# GPS-Board.net
KiCad netlist of a schematic drawn in Altium Designer
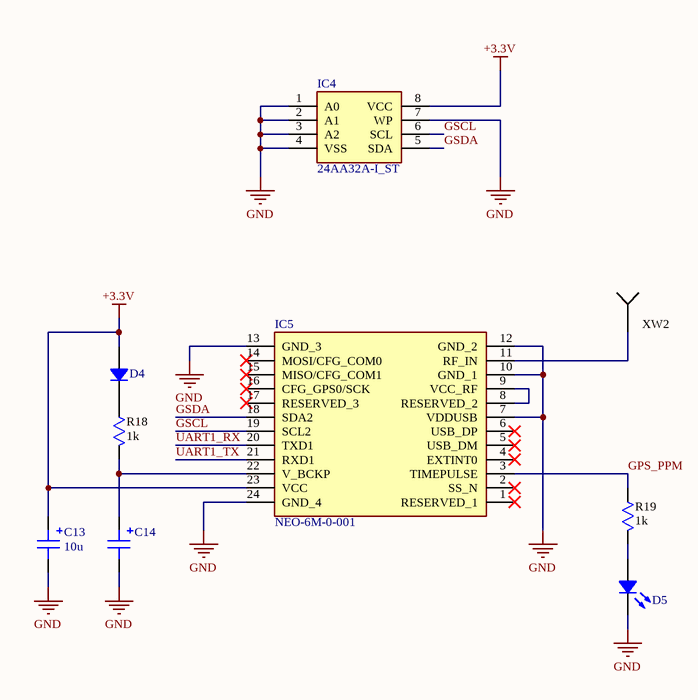
[diagram p0: GPS-Board.SchDoc]

(export (version "E")
  (design (tool "Eeschema 10.0.6"))
  (components
    (comp (ref "C13")
      (value "10u")
      (footprint "PcbLib:CAP: TANTAL-A")
      (description "SMD Capacitor Polar")
      (libsource (lib "Schlib") (part "Capacitor_polar"))
    )
    (comp (ref "C14")
      (value "~")
      (footprint "CAP: IONISTOR")
      (description "SMD Capacitor Polar")
      (libsource (lib "Schlib") (part "Capacitor_polar"))
    )
    (comp (ref "D4")
      (value "~")
      (footprint "PcbLib:DIODE: SOD323")
      (description "Rectifier Diode")
      (libsource (lib "Schlib") (part "Diode"))
    )
    (comp (ref "D5")
      (value "~")
      (footprint "PcbLib:LED 0603_1608")
      (description "Chip LED")
      (libsource (lib "Schlib") (part "LED"))
    )
    (comp (ref "IC4")
      (value "24AA32A-I_ST")
      (footprint "PcbLib:SOP65P640X120-8N")
      (description "Integrated Circuit")
      (fields
        (field (name "MANUFACTURER_PART_NUMBER") "24AA32A-I/ST")
        (field (name "MOUSER PART NUMBER") "579-24AA32A-I/ST")
      )
      (libsource (lib "*") (part "24AA32A-I_ST"))
    )
    (comp (ref "IC5")
      (value "NEO-6M-0-001")
      (footprint "PcbLib:NEO6M0001")
      (description "Integrated Circuit")
      (libsource (lib "*") (part "NEO-6M-0-001"))
    )
    (comp (ref "R18")
      (value "1k")
      (footprint "PcbLib:RES: 0603")
      (fields
        (field (name "MANUFACTURER") "Yageo")
        (field (name "PARTNUMBER") "RC0201JR-07100RL")
        (field (name "VALUEMANUFACTURERPARTNUMBER") "Resistor film, 1k, , 0201, 0.05W, -55...+125°C")
      )
      (libsource (lib "Schlib") (part "Resistor"))
    )
    (comp (ref "R19")
      (value "1k")
      (footprint "PcbLib:RES: 0603")
      (fields
        (field (name "MANUFACTURER") "Yageo")
        (field (name "PARTNUMBER") "RC0201JR-07100RL")
        (field (name "VALUEMANUFACTURERPARTNUMBER") "Resistor film, 1k, , 0201, 0.05W, -55...+125°C")
      )
      (libsource (lib "Schlib") (part "Resistor"))
    )
    (comp (ref "XW2")
      (value "~")
      (footprint "PcbLib:ANT: PCB")
      (libsource (lib "Schlib") (part "Connector RF"))
    )
  )
  (nets
    (net (code "1") (name "+3.3V") (class "Default")
      (node (ref "C13") (pin "1") (pinfunction "1_1") (pintype "passive"))
      (node (ref "D4") (pin "1") (pinfunction "1_1") (pintype "passive"))
      (node (ref "IC4") (pin "8") (pinfunction "VCC_8") (pintype "passive"))
      (node (ref "IC5") (pin "23") (pinfunction "VCC_23") (pintype "passive"))
    )
    (net (code "2") (name "/GPS_PPM") (class "Default")
      (node (ref "IC5") (pin "3") (pinfunction "TIMEPULSE_3") (pintype "passive"))
      (node (ref "R19") (pin "1") (pinfunction "1_1") (pintype "passive"))
    )
    (net (code "3") (name "/GSCL") (class "Default")
      (node (ref "IC4") (pin "6") (pinfunction "SCL_6") (pintype "passive"))
      (node (ref "IC5") (pin "19") (pinfunction "SCL2_19") (pintype "passive"))
    )
    (net (code "4") (name "/GSDA") (class "Default")
      (node (ref "IC4") (pin "5") (pinfunction "SDA_5") (pintype "passive"))
      (node (ref "IC5") (pin "18") (pinfunction "SDA2_18") (pintype "passive"))
    )
    (net (code "5") (name "/UART1_RX") (class "Default")
      (node (ref "IC5") (pin "20") (pinfunction "TXD1_20") (pintype "passive"))
    )
    (net (code "6") (name "/UART1_TX") (class "Default")
      (node (ref "IC5") (pin "21") (pinfunction "RXD1_21") (pintype "passive"))
    )
    (net (code "7") (name "GND") (class "Default")
      (node (ref "C13") (pin "2") (pinfunction "2_2") (pintype "passive"))
      (node (ref "C14") (pin "2") (pinfunction "2_2") (pintype "passive"))
      (node (ref "D5") (pin "2") (pinfunction "2_2") (pintype "passive"))
      (node (ref "IC4") (pin "1") (pinfunction "A0_1") (pintype "passive"))
      (node (ref "IC4") (pin "2") (pinfunction "A1_2") (pintype "passive"))
      (node (ref "IC4") (pin "3") (pinfunction "A2_3") (pintype "passive"))
      (node (ref "IC4") (pin "4") (pinfunction "VSS_4") (pintype "passive"))
      (node (ref "IC4") (pin "7") (pinfunction "WP_7") (pintype "passive"))
      (node (ref "IC5") (pin "10") (pinfunction "GND_1_10") (pintype "passive"))
      (node (ref "IC5") (pin "12") (pinfunction "GND_2_12") (pintype "passive"))
      (node (ref "IC5") (pin "13") (pinfunction "GND_3_13") (pintype "passive"))
      (node (ref "IC5") (pin "24") (pinfunction "GND_4_24") (pintype "passive"))
      (node (ref "IC5") (pin "7") (pinfunction "VDDUSB_7") (pintype "passive"))
    )
    (net (code "8") (name "Net-(D4-Pad2)") (class "Default")
      (node (ref "D4") (pin "2") (pinfunction "2_2") (pintype "passive"))
      (node (ref "R18") (pin "1") (pinfunction "1_1") (pintype "passive"))
    )
    (net (code "9") (name "Net-(D5-Pad1)") (class "Default")
      (node (ref "D5") (pin "1") (pinfunction "1_1") (pintype "passive"))
      (node (ref "R19") (pin "2") (pinfunction "2_2") (pintype "passive"))
    )
    (net (code "10") (name "Net-(IC5-RESERVED_2)") (class "Default")
      (node (ref "IC5") (pin "8") (pinfunction "RESERVED_2_8") (pintype "passive"))
      (node (ref "IC5") (pin "9") (pinfunction "VCC_RF_9") (pintype "passive"))
    )
    (net (code "11") (name "Net-(IC5-RF_IN)") (class "Default")
      (node (ref "IC5") (pin "11") (pinfunction "RF_IN_11") (pintype "passive"))
      (node (ref "XW2") (pin "1") (pinfunction "SIG_1") (pintype "passive"))
    )
    (net (code "12") (name "Net-(IC5-V_BCKP)") (class "Default")
      (node (ref "C14") (pin "1") (pinfunction "1_1") (pintype "passive"))
      (node (ref "IC5") (pin "22") (pinfunction "V_BCKP_22") (pintype "passive"))
      (node (ref "R18") (pin "2") (pinfunction "2_2") (pintype "passive"))
    )
    (net (code "13") (name "unconnected-(IC5-CFG_GPS0{slash}SCK-Pad16)") (class "Default")
      (node (ref "IC5") (pin "16") (pinfunction "CFG_GPS0/SCK_16") (pintype "passive+no_connect"))
    )
    (net (code "14") (name "unconnected-(IC5-EXTINT0-Pad4)") (class "Default")
      (node (ref "IC5") (pin "4") (pinfunction "EXTINT0_4") (pintype "passive+no_connect"))
    )
    (net (code "15") (name "unconnected-(IC5-MISO{slash}CFG_COM1-Pad15)") (class "Default")
      (node (ref "IC5") (pin "15") (pinfunction "MISO/CFG_COM1_15") (pintype "passive+no_connect"))
    )
    (net (code "16") (name "unconnected-(IC5-MOSI{slash}CFG_COM0-Pad14)") (class "Default")
      (node (ref "IC5") (pin "14") (pinfunction "MOSI/CFG_COM0_14") (pintype "passive+no_connect"))
    )
    (net (code "17") (name "unconnected-(IC5-RESERVED_1-Pad1)") (class "Default")
      (node (ref "IC5") (pin "1") (pinfunction "RESERVED_1_1") (pintype "passive+no_connect"))
    )
    (net (code "18") (name "unconnected-(IC5-RESERVED_3-Pad17)") (class "Default")
      (node (ref "IC5") (pin "17") (pinfunction "RESERVED_3_17") (pintype "passive+no_connect"))
    )
    (net (code "19") (name "unconnected-(IC5-SS_N-Pad2)") (class "Default")
      (node (ref "IC5") (pin "2") (pinfunction "SS_N_2") (pintype "passive+no_connect"))
    )
    (net (code "20") (name "unconnected-(IC5-USB_DM-Pad5)") (class "Default")
      (node (ref "IC5") (pin "5") (pinfunction "USB_DM_5") (pintype "passive+no_connect"))
    )
    (net (code "21") (name "unconnected-(IC5-USB_DP-Pad6)") (class "Default")
      (node (ref "IC5") (pin "6") (pinfunction "USB_DP_6") (pintype "passive+no_connect"))
    )
  )
)
